# P_06__LPDDR4.net
KiCad netlist of a schematic drawn in Altium Designer
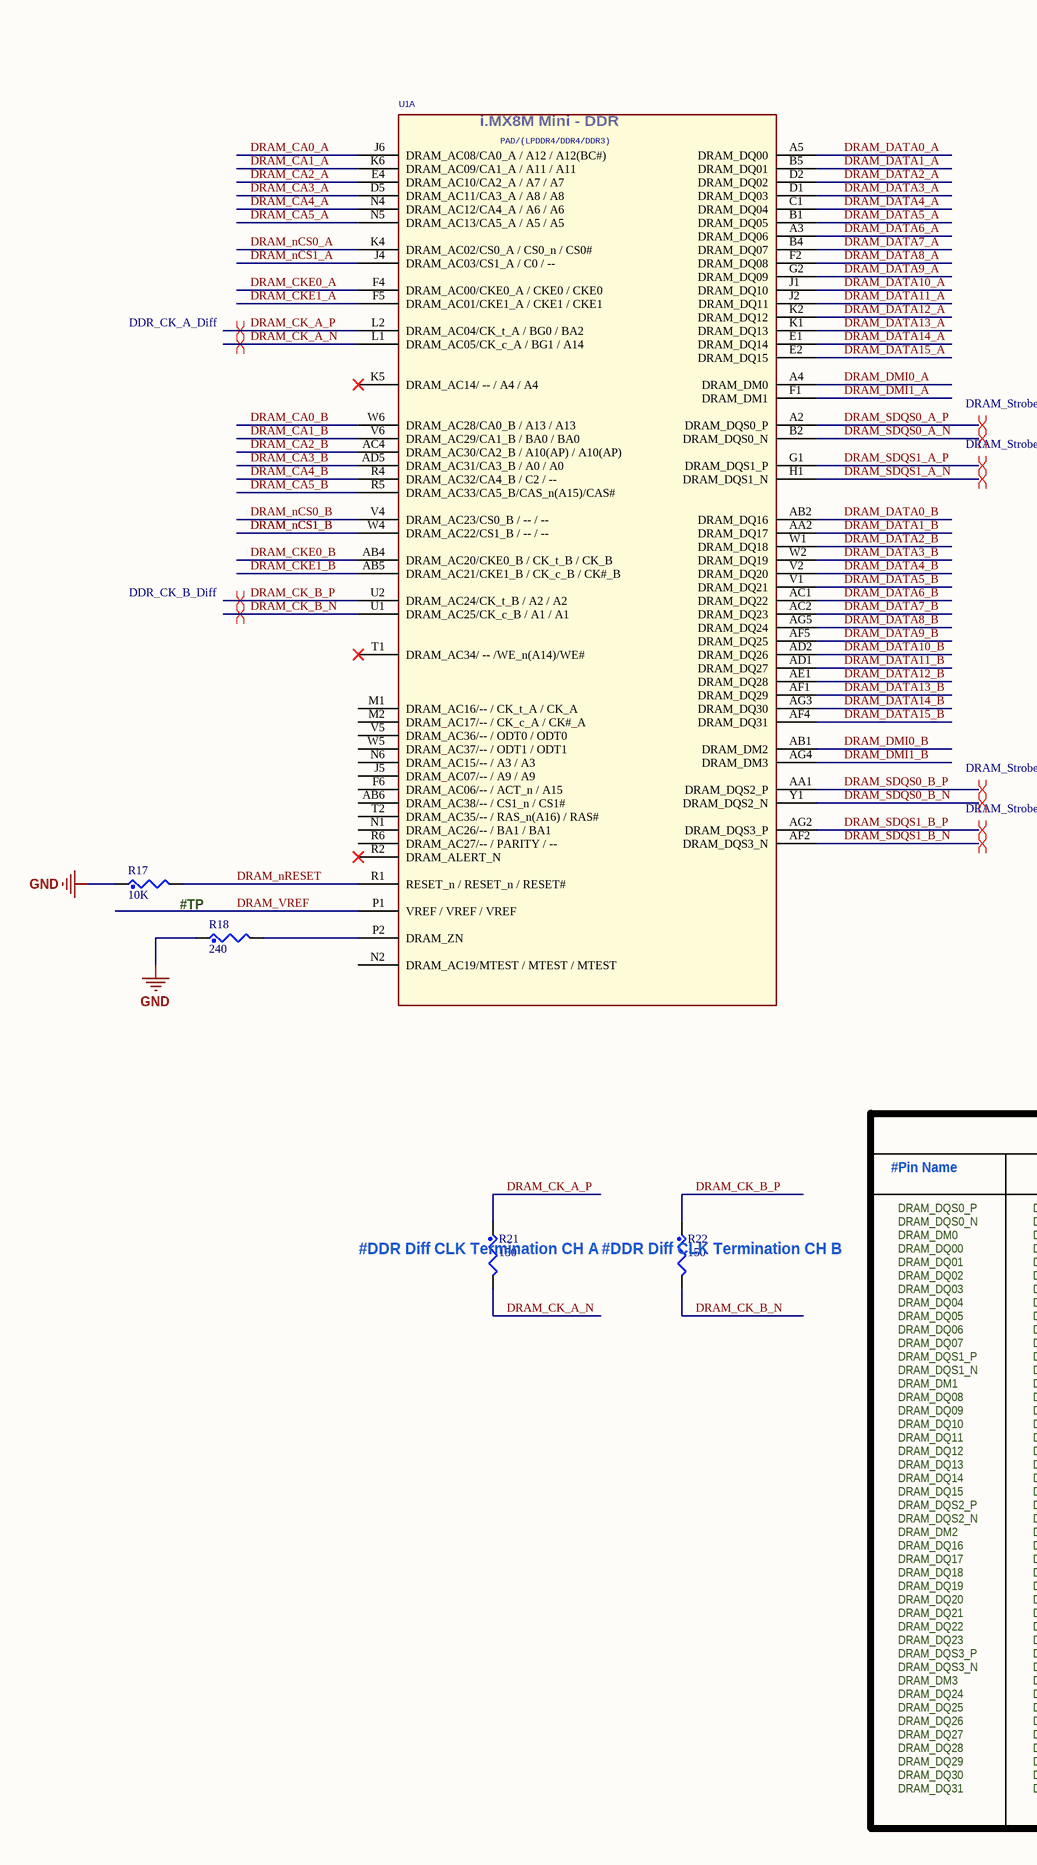
[diagram p0: P[06]_LPDDR4.SchDoc, left]
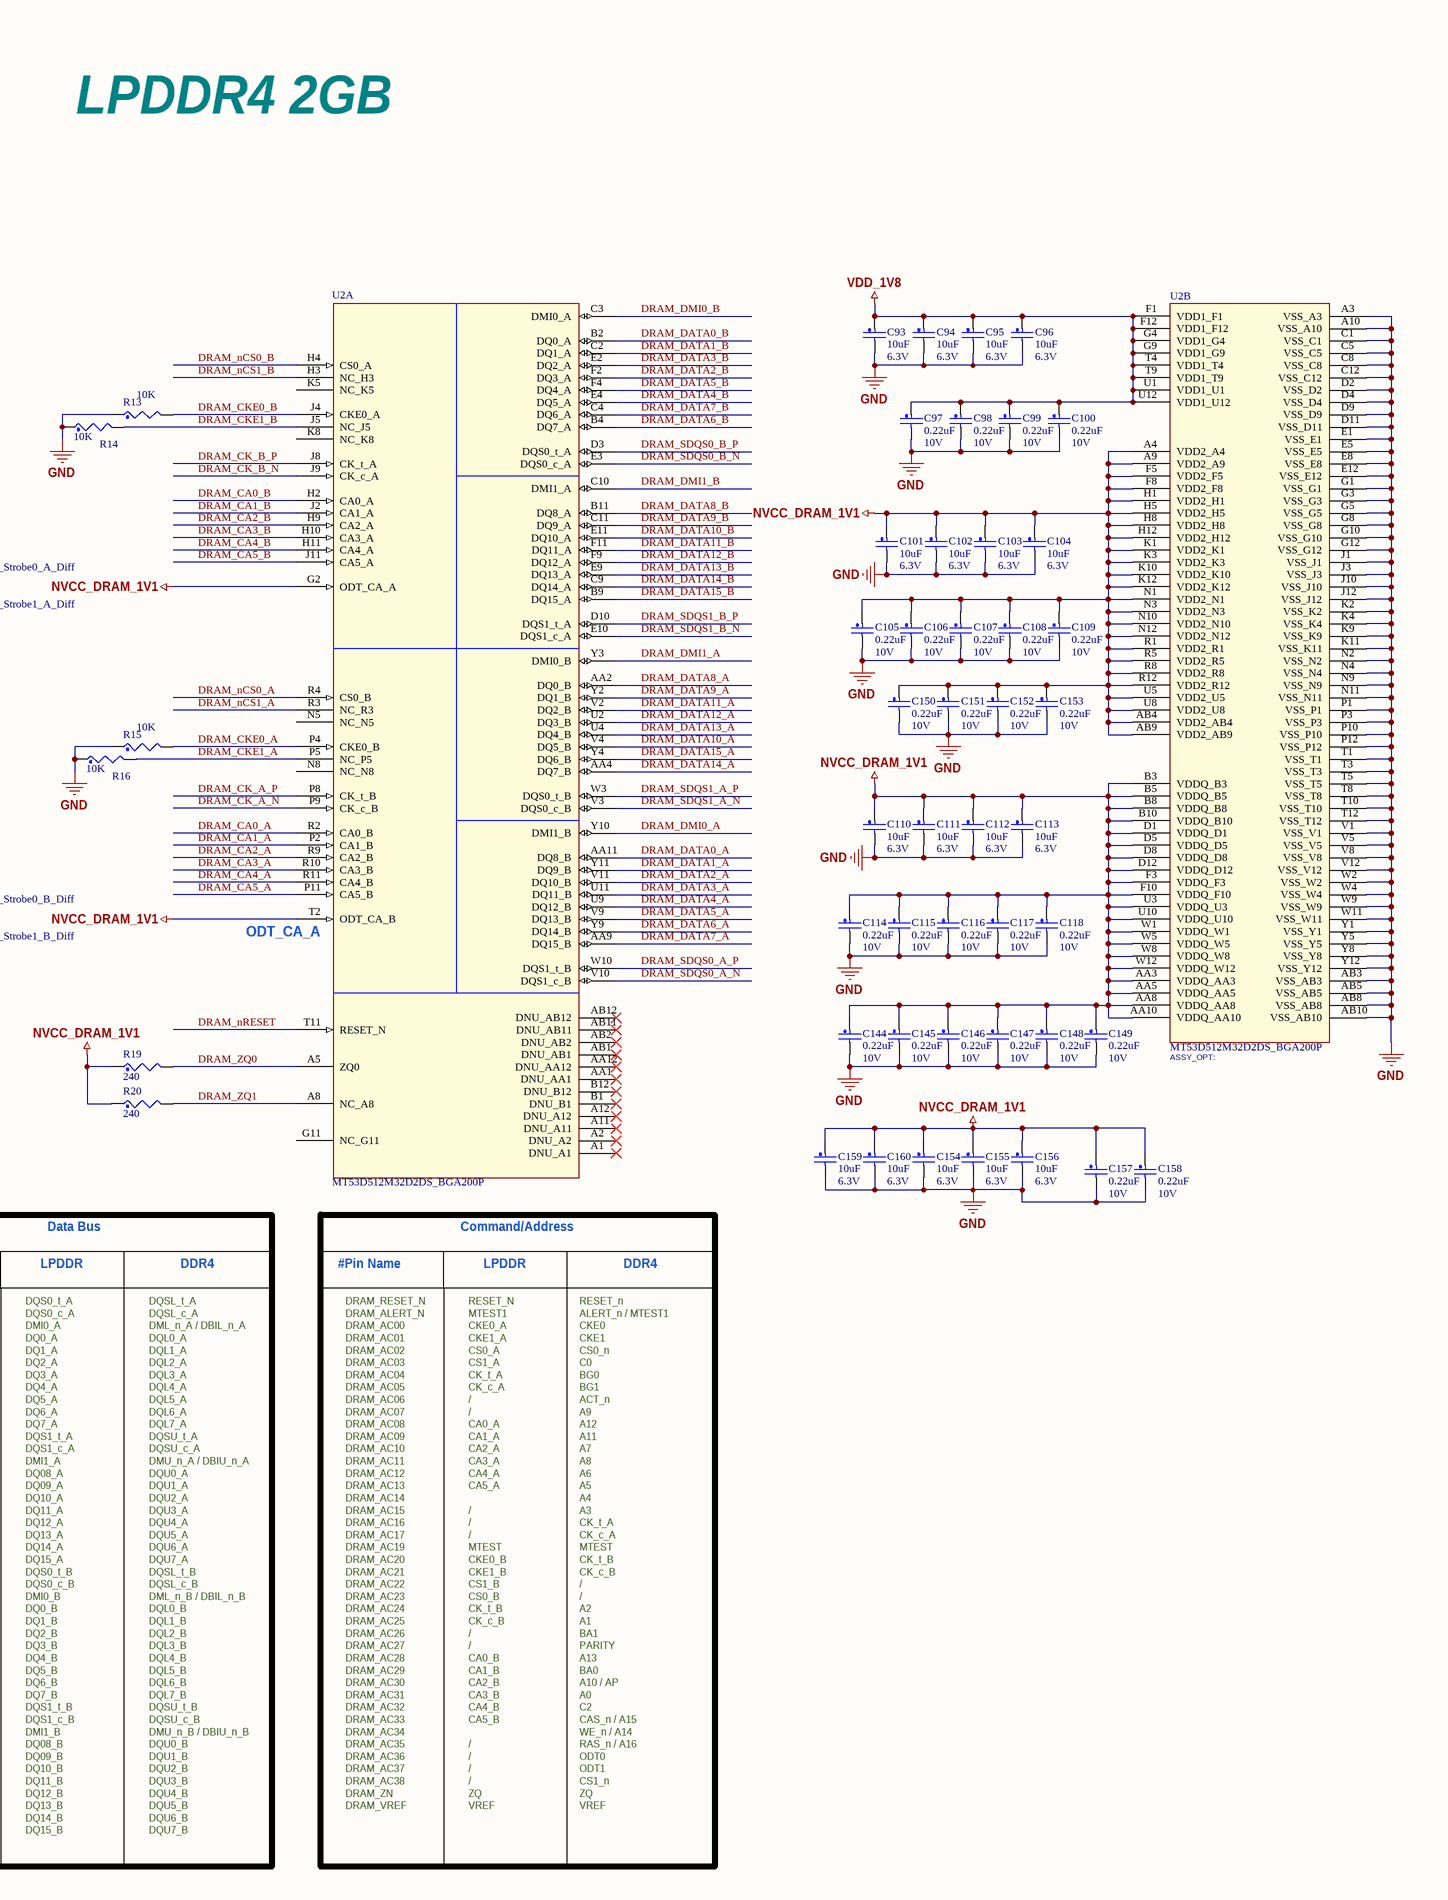
[diagram p1: P[06]_LPDDR4.SchDoc, right]

(export (version "E")
  (design (tool "Eeschema 10.0.6"))
  (components
    (comp (ref "C93")
      (value "10uF")
      (footprint "0402_CC - C")
      (fields (field (name "VOLTAGE") "6.3V"))
      (libsource (lib "AA_iMX8_M_") (part "CAP_NP"))
    )
    (comp (ref "C94")
      (value "10uF")
      (footprint "0402_CC - C")
      (fields (field (name "VOLTAGE") "6.3V"))
      (libsource (lib "AA_iMX8_M_") (part "CAP_NP"))
    )
    (comp (ref "C95")
      (value "10uF")
      (footprint "0402_CC - C")
      (fields (field (name "VOLTAGE") "6.3V"))
      (libsource (lib "AA_iMX8_M_") (part "CAP_NP"))
    )
    (comp (ref "C96")
      (value "10uF")
      (footprint "0402_CC - C")
      (fields (field (name "VOLTAGE") "6.3V"))
      (libsource (lib "AA_iMX8_M_") (part "CAP_NP"))
    )
    (comp (ref "C97")
      (value "0.22uF")
      (footprint "0201_CC - C")
      (fields (field (name "VOLTAGE") "10V"))
      (libsource (lib "AA_iMX8_M_") (part "CAP_NP"))
    )
    (comp (ref "C98")
      (value "0.22uF")
      (footprint "0201_CC - C")
      (fields (field (name "VOLTAGE") "10V"))
      (libsource (lib "AA_iMX8_M_") (part "CAP_NP"))
    )
    (comp (ref "C99")
      (value "0.22uF")
      (footprint "0201_CC - C")
      (fields (field (name "VOLTAGE") "10V"))
      (libsource (lib "AA_iMX8_M_") (part "CAP_NP"))
    )
    (comp (ref "C100")
      (value "0.22uF")
      (footprint "0201_CC - C")
      (fields (field (name "VOLTAGE") "10V"))
      (libsource (lib "AA_iMX8_M_") (part "CAP_NP"))
    )
    (comp (ref "C101")
      (value "10uF")
      (footprint "0402_CC - C")
      (fields (field (name "VOLTAGE") "6.3V"))
      (libsource (lib "AA_iMX8_M_") (part "CAP_NP"))
    )
    (comp (ref "C102")
      (value "10uF")
      (footprint "0402_CC - C")
      (fields (field (name "VOLTAGE") "6.3V"))
      (libsource (lib "AA_iMX8_M_") (part "CAP_NP"))
    )
    (comp (ref "C103")
      (value "10uF")
      (footprint "0402_CC - C")
      (fields (field (name "VOLTAGE") "6.3V"))
      (libsource (lib "AA_iMX8_M_") (part "CAP_NP"))
    )
    (comp (ref "C104")
      (value "10uF")
      (footprint "0402_CC - C")
      (fields (field (name "VOLTAGE") "6.3V"))
      (libsource (lib "AA_iMX8_M_") (part "CAP_NP"))
    )
    (comp (ref "C105")
      (value "0.22uF")
      (footprint "0201_CC - C")
      (fields (field (name "VOLTAGE") "10V"))
      (libsource (lib "AA_iMX8_M_") (part "CAP_NP"))
    )
    (comp (ref "C106")
      (value "0.22uF")
      (footprint "0201_CC - C")
      (fields (field (name "VOLTAGE") "10V"))
      (libsource (lib "AA_iMX8_M_") (part "CAP_NP"))
    )
    (comp (ref "C107")
      (value "0.22uF")
      (footprint "0201_CC - C")
      (fields (field (name "VOLTAGE") "10V"))
      (libsource (lib "AA_iMX8_M_") (part "CAP_NP"))
    )
    (comp (ref "C108")
      (value "0.22uF")
      (footprint "0201_CC - C")
      (fields (field (name "VOLTAGE") "10V"))
      (libsource (lib "AA_iMX8_M_") (part "CAP_NP"))
    )
    (comp (ref "C109")
      (value "0.22uF")
      (footprint "0201_CC - C")
      (fields (field (name "VOLTAGE") "10V"))
      (libsource (lib "AA_iMX8_M_") (part "CAP_NP"))
    )
    (comp (ref "C110")
      (value "10uF")
      (footprint "0402_CC - C")
      (fields (field (name "VOLTAGE") "6.3V"))
      (libsource (lib "AA_iMX8_M_") (part "CAP_NP"))
    )
    (comp (ref "C111")
      (value "10uF")
      (footprint "0402_CC - C")
      (fields (field (name "VOLTAGE") "6.3V"))
      (libsource (lib "AA_iMX8_M_") (part "CAP_NP"))
    )
    (comp (ref "C112")
      (value "10uF")
      (footprint "0402_CC - C")
      (fields (field (name "VOLTAGE") "6.3V"))
      (libsource (lib "AA_iMX8_M_") (part "CAP_NP"))
    )
    (comp (ref "C113")
      (value "10uF")
      (footprint "0402_CC - C")
      (fields (field (name "VOLTAGE") "6.3V"))
      (libsource (lib "AA_iMX8_M_") (part "CAP_NP"))
    )
    (comp (ref "C114")
      (value "0.22uF")
      (footprint "0201_CC - C")
      (fields (field (name "VOLTAGE") "10V"))
      (libsource (lib "AA_iMX8_M_") (part "CAP_NP"))
    )
    (comp (ref "C115")
      (value "0.22uF")
      (footprint "0201_CC - C")
      (fields (field (name "VOLTAGE") "10V"))
      (libsource (lib "AA_iMX8_M_") (part "CAP_NP"))
    )
    (comp (ref "C116")
      (value "0.22uF")
      (footprint "0201_CC - C")
      (fields (field (name "VOLTAGE") "10V"))
      (libsource (lib "AA_iMX8_M_") (part "CAP_NP"))
    )
    (comp (ref "C117")
      (value "0.22uF")
      (footprint "0201_CC - C")
      (fields (field (name "VOLTAGE") "10V"))
      (libsource (lib "AA_iMX8_M_") (part "CAP_NP"))
    )
    (comp (ref "C118")
      (value "0.22uF")
      (footprint "0201_CC - C")
      (fields (field (name "VOLTAGE") "10V"))
      (libsource (lib "AA_iMX8_M_") (part "CAP_NP"))
    )
    (comp (ref "C144")
      (value "0.22uF")
      (footprint "0201_CC - C")
      (fields (field (name "VOLTAGE") "10V"))
      (libsource (lib "AA_iMX8_M_") (part "CAP_NP"))
    )
    (comp (ref "C145")
      (value "0.22uF")
      (footprint "0201_CC - C")
      (fields (field (name "VOLTAGE") "10V"))
      (libsource (lib "AA_iMX8_M_") (part "CAP_NP"))
    )
    (comp (ref "C146")
      (value "0.22uF")
      (footprint "0201_CC - C")
      (fields (field (name "VOLTAGE") "10V"))
      (libsource (lib "AA_iMX8_M_") (part "CAP_NP"))
    )
    (comp (ref "C147")
      (value "0.22uF")
      (footprint "0201_CC - C")
      (fields (field (name "VOLTAGE") "10V"))
      (libsource (lib "AA_iMX8_M_") (part "CAP_NP"))
    )
    (comp (ref "C148")
      (value "0.22uF")
      (footprint "0201_CC - C")
      (fields (field (name "VOLTAGE") "10V"))
      (libsource (lib "AA_iMX8_M_") (part "CAP_NP"))
    )
    (comp (ref "C149")
      (value "0.22uF")
      (footprint "0201_CC - C")
      (fields (field (name "VOLTAGE") "10V"))
      (libsource (lib "AA_iMX8_M_") (part "CAP_NP"))
    )
    (comp (ref "C150")
      (value "0.22uF")
      (footprint "0201_CC - C")
      (fields (field (name "VOLTAGE") "10V"))
      (libsource (lib "AA_iMX8_M_") (part "CAP_NP"))
    )
    (comp (ref "C151")
      (value "0.22uF")
      (footprint "0201_CC - C")
      (fields (field (name "VOLTAGE") "10V"))
      (libsource (lib "AA_iMX8_M_") (part "CAP_NP"))
    )
    (comp (ref "C152")
      (value "0.22uF")
      (footprint "0201_CC - C")
      (fields (field (name "VOLTAGE") "10V"))
      (libsource (lib "AA_iMX8_M_") (part "CAP_NP"))
    )
    (comp (ref "C153")
      (value "0.22uF")
      (footprint "0201_CC - C")
      (fields (field (name "VOLTAGE") "10V"))
      (libsource (lib "AA_iMX8_M_") (part "CAP_NP"))
    )
    (comp (ref "C154")
      (value "10uF")
      (footprint "0402_CC - C")
      (fields (field (name "VOLTAGE") "6.3V"))
      (libsource (lib "AA_iMX8_M_") (part "CAP_NP"))
    )
    (comp (ref "C155")
      (value "10uF")
      (footprint "0402_CC - C")
      (fields (field (name "VOLTAGE") "6.3V"))
      (libsource (lib "AA_iMX8_M_") (part "CAP_NP"))
    )
    (comp (ref "C156")
      (value "10uF")
      (footprint "0402_CC - C")
      (fields (field (name "VOLTAGE") "6.3V"))
      (libsource (lib "AA_iMX8_M_") (part "CAP_NP"))
    )
    (comp (ref "C157")
      (value "0.22uF")
      (footprint "0201_CC - C")
      (fields (field (name "VOLTAGE") "10V"))
      (libsource (lib "AA_iMX8_M_") (part "CAP_NP"))
    )
    (comp (ref "C158")
      (value "0.22uF")
      (footprint "0201_CC - C")
      (fields (field (name "VOLTAGE") "10V"))
      (libsource (lib "AA_iMX8_M_") (part "CAP_NP"))
    )
    (comp (ref "C159")
      (value "10uF")
      (footprint "0402_CC - C")
      (fields (field (name "VOLTAGE") "6.3V"))
      (libsource (lib "AA_iMX8_M_") (part "CAP_NP"))
    )
    (comp (ref "C160")
      (value "10uF")
      (footprint "0402_CC - C")
      (fields (field (name "VOLTAGE") "6.3V"))
      (libsource (lib "AA_iMX8_M_") (part "CAP_NP"))
    )
    (comp (ref "R13") (value "10K") (footprint "0201_CC") (libsource (lib "AA_iMX8_M_") (part "RES")))
    (comp (ref "R14") (value "10K") (footprint "0201_CC") (libsource (lib "AA_iMX8_M_") (part "RES")))
    (comp (ref "R15") (value "10K") (footprint "0201_CC") (libsource (lib "AA_iMX8_M_") (part "RES")))
    (comp (ref "R16") (value "10K") (footprint "0201_CC") (libsource (lib "AA_iMX8_M_") (part "RES")))
    (comp (ref "R17") (value "10K") (footprint "0201_CC") (libsource (lib "AA_iMX8_M_") (part "RES")))
    (comp (ref "R18") (value "240") (footprint "0201_CC") (libsource (lib "AA_iMX8_M_") (part "RES")))
    (comp (ref "R19") (value "240") (footprint "0201_CC") (libsource (lib "AA_iMX8_M_") (part "RES")))
    (comp (ref "R20") (value "240") (footprint "0201_CC") (libsource (lib "AA_iMX8_M_") (part "RES")))
    (comp (ref "R21") (value "150") (footprint "0402_CC") (libsource (lib "AA_iMX8_M_") (part "RES")))
    (comp (ref "R22") (value "150") (footprint "0402_CC") (libsource (lib "AA_iMX8_M_") (part "RES")))
    (comp (ref "U1")
      (value "~")
      (footprint "BGA486_0P5_14X14")
      (description "IC CPU QUAD CORTEX A53+M4 1.8GHZ BGA486 / By Arman Arvand")
      (libsource (lib "AA_iMX8_M_") (part "MIMX8MM_BGA486P"))
    )
    (comp (ref "U2")
      (value "MT53D512M32D2DS_BGA200P")
      (footprint "BGA200_0P65X0P8_10P1X14P6")
      (description "MT53D512M32D2DS_BGA200P\\By AAR")
      (libsource (lib "AA_iMX8_M_") (part "MT53D512M32D2DS_BGA200P"))
    )
  )
  (nets
    (net (code "1") (name "/DRAM_CA0_A") (class "Default")
      (node (ref "U1") (pin "J6") (pinfunction "DRAM_AC08/CA0_A_/_A12_/_A12(BC#)_J6") (pintype "passive"))
      (node (ref "U2") (pin "R2") (pinfunction "CA0_B_R2") (pintype "input"))
    )
    (net (code "2") (name "/DRAM_CA0_B") (class "Default")
      (node (ref "U1") (pin "W6") (pinfunction "DRAM_AC28/CA0_B_/_A13_/_A13_W6") (pintype "passive"))
      (node (ref "U2") (pin "H2") (pinfunction "CA0_A_H2") (pintype "input"))
    )
    (net (code "3") (name "/DRAM_CA1_A") (class "Default")
      (node (ref "U1") (pin "K6") (pinfunction "DRAM_AC09/CA1_A_/_A11_/_A11_K6") (pintype "passive"))
      (node (ref "U2") (pin "P2") (pinfunction "CA1_B_P2") (pintype "input"))
    )
    (net (code "4") (name "/DRAM_CA1_B") (class "Default")
      (node (ref "U1") (pin "V6") (pinfunction "DRAM_AC29/CA1_B_/_BA0_/_BA0_V6") (pintype "passive"))
      (node (ref "U2") (pin "J2") (pinfunction "CA1_A_J2") (pintype "input"))
    )
    (net (code "5") (name "/DRAM_CA2_A") (class "Default")
      (node (ref "U1") (pin "E4") (pinfunction "DRAM_AC10/CA2_A_/_A7_/_A7_E4") (pintype "passive"))
      (node (ref "U2") (pin "R9") (pinfunction "CA2_B_R9") (pintype "input"))
    )
    (net (code "6") (name "/DRAM_CA2_B") (class "Default")
      (node (ref "U1") (pin "AC4") (pinfunction "DRAM_AC30/CA2_B_/_A10(AP)_/_A10(AP)_AC4") (pintype "passive"))
      (node (ref "U2") (pin "H9") (pinfunction "CA2_A_H9") (pintype "input"))
    )
    (net (code "7") (name "/DRAM_CA3_A") (class "Default")
      (node (ref "U1") (pin "D5") (pinfunction "DRAM_AC11/CA3_A_/_A8_/_A8_D5") (pintype "passive"))
      (node (ref "U2") (pin "R10") (pinfunction "CA3_B_R10") (pintype "input"))
    )
    (net (code "8") (name "/DRAM_CA3_B") (class "Default")
      (node (ref "U1") (pin "AD5") (pinfunction "DRAM_AC31/CA3_B_/_A0_/_A0_AD5") (pintype "passive"))
      (node (ref "U2") (pin "H10") (pinfunction "CA3_A_H10") (pintype "input"))
    )
    (net (code "9") (name "/DRAM_CA4_A") (class "Default")
      (node (ref "U1") (pin "N4") (pinfunction "DRAM_AC12/CA4_A_/_A6_/_A6_N4") (pintype "passive"))
      (node (ref "U2") (pin "R11") (pinfunction "CA4_B_R11") (pintype "input"))
    )
    (net (code "10") (name "/DRAM_CA4_B") (class "Default")
      (node (ref "U1") (pin "R4") (pinfunction "DRAM_AC32/CA4_B_/_C2_/_--_R4") (pintype "passive"))
      (node (ref "U2") (pin "H11") (pinfunction "CA4_A_H11") (pintype "input"))
    )
    (net (code "11") (name "/DRAM_CA5_A") (class "Default")
      (node (ref "U1") (pin "N5") (pinfunction "DRAM_AC13/CA5_A_/_A5_/_A5_N5") (pintype "passive"))
      (node (ref "U2") (pin "P11") (pinfunction "CA5_B_P11") (pintype "input"))
    )
    (net (code "12") (name "/DRAM_CA5_B") (class "Default")
      (node (ref "U1") (pin "R5") (pinfunction "DRAM_AC33/CA5_B/CAS_n(A15)/CAS#_R5") (pintype "passive"))
      (node (ref "U2") (pin "J11") (pinfunction "CA5_A_J11") (pintype "input"))
    )
    (net (code "13") (name "/DRAM_CKE0_A") (class "Default")
      (node (ref "R15") (pin "2") (pinfunction "2_2") (pintype "passive"))
      (node (ref "U1") (pin "F4") (pinfunction "DRAM_AC00/CKE0_A_/_CKE0_/_CKE0_F4") (pintype "passive"))
      (node (ref "U2") (pin "P4") (pinfunction "CKE0_B_P4") (pintype "input"))
    )
    (net (code "14") (name "/DRAM_CKE0_B") (class "Default")
      (node (ref "R13") (pin "2") (pinfunction "2_2") (pintype "passive"))
      (node (ref "U1") (pin "AB4") (pinfunction "DRAM_AC20/CKE0_B_/_CK_t_B_/_CK_B_AB4") (pintype "passive"))
      (node (ref "U2") (pin "J4") (pinfunction "CKE0_A_J4") (pintype "input"))
    )
    (net (code "15") (name "/DRAM_CKE1_A") (class "Default")
      (node (ref "R16") (pin "2") (pinfunction "2_2") (pintype "passive"))
      (node (ref "U1") (pin "F5") (pinfunction "DRAM_AC01/CKE1_A_/_CKE1_/_CKE1_F5") (pintype "passive"))
      (node (ref "U2") (pin "P5") (pinfunction "NC_P5_P5") (pintype "passive"))
    )
    (net (code "16") (name "/DRAM_CKE1_B") (class "Default")
      (node (ref "R14") (pin "2") (pinfunction "2_2") (pintype "passive"))
      (node (ref "U1") (pin "AB5") (pinfunction "DRAM_AC21/CKE1_B_/_CK_c_B_/_CK#_B_AB5") (pintype "passive"))
      (node (ref "U2") (pin "J5") (pinfunction "NC_J5_J5") (pintype "passive"))
    )
    (net (code "17") (name "/DRAM_CK_A_N") (class "Default")
      (node (ref "R21") (pin "2") (pinfunction "2_2") (pintype "passive"))
      (node (ref "U1") (pin "L1") (pinfunction "DRAM_AC05/CK_c_A_/_BG1_/_A14_L1") (pintype "passive"))
      (node (ref "U2") (pin "P9") (pinfunction "CK_c_B_P9") (pintype "input"))
    )
    (net (code "18") (name "/DRAM_CK_A_P") (class "Default")
      (node (ref "R21") (pin "1") (pinfunction "1_1") (pintype "passive"))
      (node (ref "U1") (pin "L2") (pinfunction "DRAM_AC04/CK_t_A_/_BG0_/_BA2_L2") (pintype "passive"))
      (node (ref "U2") (pin "P8") (pinfunction "CK_t_B_P8") (pintype "input"))
    )
    (net (code "19") (name "/DRAM_CK_B_N") (class "Default")
      (node (ref "R22") (pin "2") (pinfunction "2_2") (pintype "passive"))
      (node (ref "U1") (pin "U1") (pinfunction "DRAM_AC25/CK_c_B_/_A1_/_A1_U1") (pintype "passive"))
      (node (ref "U2") (pin "J9") (pinfunction "CK_c_A_J9") (pintype "input"))
    )
    (net (code "20") (name "/DRAM_CK_B_P") (class "Default")
      (node (ref "R22") (pin "1") (pinfunction "1_1") (pintype "passive"))
      (node (ref "U1") (pin "U2") (pinfunction "DRAM_AC24/CK_t_B_/_A2_/_A2_U2") (pintype "passive"))
      (node (ref "U2") (pin "J8") (pinfunction "CK_t_A_J8") (pintype "input"))
    )
    (net (code "21") (name "/DRAM_DATA0_A") (class "Default")
      (node (ref "U1") (pin "A5") (pinfunction "DRAM_DQ00_A5") (pintype "passive"))
      (node (ref "U2") (pin "AA11") (pinfunction "DQ8_B_AA11") (pintype "bidirectional"))
    )
    (net (code "22") (name "/DRAM_DATA0_B") (class "Default")
      (node (ref "U1") (pin "AB2") (pinfunction "DRAM_DQ16_AB2") (pintype "passive"))
      (node (ref "U2") (pin "B2") (pinfunction "DQ0_A_B2") (pintype "bidirectional"))
    )
    (net (code "23") (name "/DRAM_DATA1_A") (class "Default")
      (node (ref "U1") (pin "B5") (pinfunction "DRAM_DQ01_B5") (pintype "passive"))
      (node (ref "U2") (pin "Y11") (pinfunction "DQ9_B_Y11") (pintype "bidirectional"))
    )
    (net (code "24") (name "/DRAM_DATA1_B") (class "Default")
      (node (ref "U1") (pin "AA2") (pinfunction "DRAM_DQ17_AA2") (pintype "passive"))
      (node (ref "U2") (pin "C2") (pinfunction "DQ1_A_C2") (pintype "bidirectional"))
    )
    (net (code "25") (name "/DRAM_DATA2_A") (class "Default")
      (node (ref "U1") (pin "D2") (pinfunction "DRAM_DQ02_D2") (pintype "passive"))
      (node (ref "U2") (pin "V11") (pinfunction "DQ10_B_V11") (pintype "bidirectional"))
    )
    (net (code "26") (name "/DRAM_DATA2_B") (class "Default")
      (node (ref "U1") (pin "W1") (pinfunction "DRAM_DQ18_W1") (pintype "passive"))
      (node (ref "U2") (pin "F2") (pinfunction "DQ3_A_F2") (pintype "bidirectional"))
    )
    (net (code "27") (name "/DRAM_DATA3_A") (class "Default")
      (node (ref "U1") (pin "D1") (pinfunction "DRAM_DQ03_D1") (pintype "passive"))
      (node (ref "U2") (pin "U11") (pinfunction "DQ11_B_U11") (pintype "bidirectional"))
    )
    (net (code "28") (name "/DRAM_DATA3_B") (class "Default")
      (node (ref "U1") (pin "W2") (pinfunction "DRAM_DQ19_W2") (pintype "passive"))
      (node (ref "U2") (pin "E2") (pinfunction "DQ2_A_E2") (pintype "bidirectional"))
    )
    (net (code "29") (name "/DRAM_DATA4_A") (class "Default")
      (node (ref "U1") (pin "C1") (pinfunction "DRAM_DQ04_C1") (pintype "passive"))
      (node (ref "U2") (pin "U9") (pinfunction "DQ12_B_U9") (pintype "bidirectional"))
    )
    (net (code "30") (name "/DRAM_DATA4_B") (class "Default")
      (node (ref "U1") (pin "V2") (pinfunction "DRAM_DQ20_V2") (pintype "passive"))
      (node (ref "U2") (pin "E4") (pinfunction "DQ5_A_E4") (pintype "bidirectional"))
    )
    (net (code "31") (name "/DRAM_DATA5_A") (class "Default")
      (node (ref "U1") (pin "B1") (pinfunction "DRAM_DQ05_B1") (pintype "passive"))
      (node (ref "U2") (pin "V9") (pinfunction "DQ13_B_V9") (pintype "bidirectional"))
    )
    (net (code "32") (name "/DRAM_DATA5_B") (class "Default")
      (node (ref "U1") (pin "V1") (pinfunction "DRAM_DQ21_V1") (pintype "passive"))
      (node (ref "U2") (pin "F4") (pinfunction "DQ4_A_F4") (pintype "bidirectional"))
    )
    (net (code "33") (name "/DRAM_DATA6_A") (class "Default")
      (node (ref "U1") (pin "A3") (pinfunction "DRAM_DQ06_A3") (pintype "passive"))
      (node (ref "U2") (pin "Y9") (pinfunction "DQ14_B_Y9") (pintype "bidirectional"))
    )
    (net (code "34") (name "/DRAM_DATA6_B") (class "Default")
      (node (ref "U1") (pin "AC1") (pinfunction "DRAM_DQ22_AC1") (pintype "passive"))
      (node (ref "U2") (pin "B4") (pinfunction "DQ7_A_B4") (pintype "bidirectional"))
    )
    (net (code "35") (name "/DRAM_DATA7_A") (class "Default")
      (node (ref "U1") (pin "B4") (pinfunction "DRAM_DQ07_B4") (pintype "passive"))
      (node (ref "U2") (pin "AA9") (pinfunction "DQ15_B_AA9") (pintype "bidirectional"))
    )
    (net (code "36") (name "/DRAM_DATA7_B") (class "Default")
      (node (ref "U1") (pin "AC2") (pinfunction "DRAM_DQ23_AC2") (pintype "passive"))
      (node (ref "U2") (pin "C4") (pinfunction "DQ6_A_C4") (pintype "bidirectional"))
    )
    (net (code "37") (name "/DRAM_DATA8_A") (class "Default")
      (node (ref "U1") (pin "F2") (pinfunction "DRAM_DQ08_F2") (pintype "passive"))
      (node (ref "U2") (pin "AA2") (pinfunction "DQ0_B_AA2") (pintype "bidirectional"))
    )
    (net (code "38") (name "/DRAM_DATA8_B") (class "Default")
      (node (ref "U1") (pin "AG5") (pinfunction "DRAM_DQ24_AG5") (pintype "passive"))
      (node (ref "U2") (pin "B11") (pinfunction "DQ8_A_B11") (pintype "bidirectional"))
    )
    (net (code "39") (name "/DRAM_DATA9_A") (class "Default")
      (node (ref "U1") (pin "G2") (pinfunction "DRAM_DQ09_G2") (pintype "passive"))
      (node (ref "U2") (pin "Y2") (pinfunction "DQ1_B_Y2") (pintype "bidirectional"))
    )
    (net (code "40") (name "/DRAM_DATA9_B") (class "Default")
      (node (ref "U1") (pin "AF5") (pinfunction "DRAM_DQ25_AF5") (pintype "passive"))
      (node (ref "U2") (pin "C11") (pinfunction "DQ9_A_C11") (pintype "bidirectional"))
    )
    (net (code "41") (name "/DRAM_DATA10_A") (class "Default")
      (node (ref "U1") (pin "J1") (pinfunction "DRAM_DQ10_J1") (pintype "passive"))
      (node (ref "U2") (pin "V4") (pinfunction "DQ5_B_V4") (pintype "bidirectional"))
    )
    (net (code "42") (name "/DRAM_DATA10_B") (class "Default")
      (node (ref "U1") (pin "AD2") (pinfunction "DRAM_DQ26_AD2") (pintype "passive"))
      (node (ref "U2") (pin "E11") (pinfunction "DQ10_A_E11") (pintype "bidirectional"))
    )
    (net (code "43") (name "/DRAM_DATA11_A") (class "Default")
      (node (ref "U1") (pin "J2") (pinfunction "DRAM_DQ11_J2") (pintype "passive"))
      (node (ref "U2") (pin "V2") (pinfunction "DQ2_B_V2") (pintype "bidirectional"))
    )
    (net (code "44") (name "/DRAM_DATA11_B") (class "Default")
      (node (ref "U1") (pin "AD1") (pinfunction "DRAM_DQ27_AD1") (pintype "passive"))
      (node (ref "U2") (pin "F11") (pinfunction "DQ11_A_F11") (pintype "bidirectional"))
    )
    (net (code "45") (name "/DRAM_DATA12_A") (class "Default")
      (node (ref "U1") (pin "K2") (pinfunction "DRAM_DQ12_K2") (pintype "passive"))
      (node (ref "U2") (pin "U2") (pinfunction "DQ3_B_U2") (pintype "bidirectional"))
    )
    (net (code "46") (name "/DRAM_DATA12_B") (class "Default")
      (node (ref "U1") (pin "AE1") (pinfunction "DRAM_DQ28_AE1") (pintype "passive"))
      (node (ref "U2") (pin "F9") (pinfunction "DQ12_A_F9") (pintype "bidirectional"))
    )
    (net (code "47") (name "/DRAM_DATA13_A") (class "Default")
      (node (ref "U1") (pin "K1") (pinfunction "DRAM_DQ13_K1") (pintype "passive"))
      (node (ref "U2") (pin "U4") (pinfunction "DQ4_B_U4") (pintype "bidirectional"))
    )
    (net (code "48") (name "/DRAM_DATA13_B") (class "Default")
      (node (ref "U1") (pin "AF1") (pinfunction "DRAM_DQ29_AF1") (pintype "passive"))
      (node (ref "U2") (pin "E9") (pinfunction "DQ13_A_E9") (pintype "bidirectional"))
    )
    (net (code "49") (name "/DRAM_DATA14_A") (class "Default")
      (node (ref "U1") (pin "E1") (pinfunction "DRAM_DQ14_E1") (pintype "passive"))
      (node (ref "U2") (pin "AA4") (pinfunction "DQ7_B_AA4") (pintype "bidirectional"))
    )
    (net (code "50") (name "/DRAM_DATA14_B") (class "Default")
      (node (ref "U1") (pin "AG3") (pinfunction "DRAM_DQ30_AG3") (pintype "passive"))
      (node (ref "U2") (pin "C9") (pinfunction "DQ14_A_C9") (pintype "bidirectional"))
    )
    (net (code "51") (name "/DRAM_DATA15_A") (class "Default")
      (node (ref "U1") (pin "E2") (pinfunction "DRAM_DQ15_E2") (pintype "passive"))
      (node (ref "U2") (pin "Y4") (pinfunction "DQ6_B_Y4") (pintype "bidirectional"))
    )
    (net (code "52") (name "/DRAM_DATA15_B") (class "Default")
      (node (ref "U1") (pin "AF4") (pinfunction "DRAM_DQ31_AF4") (pintype "passive"))
      (node (ref "U2") (pin "B9") (pinfunction "DQ15_A_B9") (pintype "bidirectional"))
    )
    (net (code "53") (name "/DRAM_DMI0_A") (class "Default")
      (node (ref "U1") (pin "A4") (pinfunction "DRAM_DM0_A4") (pintype "passive"))
      (node (ref "U2") (pin "Y10") (pinfunction "DMI1_B_Y10") (pintype "bidirectional"))
    )
    (net (code "54") (name "/DRAM_DMI0_B") (class "Default")
      (node (ref "U1") (pin "AB1") (pinfunction "DRAM_DM2_AB1") (pintype "passive"))
      (node (ref "U2") (pin "C3") (pinfunction "DMI0_A_C3") (pintype "bidirectional"))
    )
    (net (code "55") (name "/DRAM_DMI1_A") (class "Default")
      (node (ref "U1") (pin "F1") (pinfunction "DRAM_DM1_F1") (pintype "passive"))
      (node (ref "U2") (pin "Y3") (pinfunction "DMI0_B_Y3") (pintype "bidirectional"))
    )
    (net (code "56") (name "/DRAM_DMI1_B") (class "Default")
      (node (ref "U1") (pin "AG4") (pinfunction "DRAM_DM3_AG4") (pintype "passive"))
      (node (ref "U2") (pin "C10") (pinfunction "DMI1_A_C10") (pintype "bidirectional"))
    )
    (net (code "57") (name "/DRAM_SDQS0_A_N") (class "Default")
      (node (ref "U1") (pin "B2") (pinfunction "DRAM_DQS0_N_B2") (pintype "passive"))
      (node (ref "U2") (pin "V10") (pinfunction "DQS1_c_B_V10") (pintype "bidirectional"))
    )
    (net (code "58") (name "/DRAM_SDQS0_A_P") (class "Default")
      (node (ref "U1") (pin "A2") (pinfunction "DRAM_DQS0_P_A2") (pintype "passive"))
      (node (ref "U2") (pin "W10") (pinfunction "DQS1_t_B_W10") (pintype "bidirectional"))
    )
    (net (code "59") (name "/DRAM_SDQS0_B_N") (class "Default")
      (node (ref "U1") (pin "Y1") (pinfunction "DRAM_DQS2_N_Y1") (pintype "passive"))
      (node (ref "U2") (pin "E3") (pinfunction "DQS0_c_A_E3") (pintype "bidirectional"))
    )
    (net (code "60") (name "/DRAM_SDQS0_B_P") (class "Default")
      (node (ref "U1") (pin "AA1") (pinfunction "DRAM_DQS2_P_AA1") (pintype "passive"))
      (node (ref "U2") (pin "D3") (pinfunction "DQS0_t_A_D3") (pintype "bidirectional"))
    )
    (net (code "61") (name "/DRAM_SDQS1_A_N") (class "Default")
      (node (ref "U1") (pin "H1") (pinfunction "DRAM_DQS1_N_H1") (pintype "passive"))
      (node (ref "U2") (pin "V3") (pinfunction "DQS0_c_B_V3") (pintype "bidirectional"))
    )
    (net (code "62") (name "/DRAM_SDQS1_A_P") (class "Default")
      (node (ref "U1") (pin "G1") (pinfunction "DRAM_DQS1_P_G1") (pintype "passive"))
      (node (ref "U2") (pin "W3") (pinfunction "DQS0_t_B_W3") (pintype "bidirectional"))
    )
    (net (code "63") (name "/DRAM_SDQS1_B_N") (class "Default")
      (node (ref "U1") (pin "AF2") (pinfunction "DRAM_DQS3_N_AF2") (pintype "passive"))
      (node (ref "U2") (pin "E10") (pinfunction "DQS1_c_A_E10") (pintype "bidirectional"))
    )
    (net (code "64") (name "/DRAM_SDQS1_B_P") (class "Default")
      (node (ref "U1") (pin "AG2") (pinfunction "DRAM_DQS3_P_AG2") (pintype "passive"))
      (node (ref "U2") (pin "D10") (pinfunction "DQS1_t_A_D10") (pintype "bidirectional"))
    )
    (net (code "65") (name "/DRAM_VREF") (class "Default")
      (node (ref "U1") (pin "P1") (pinfunction "VREF_/_VREF_/_VREF_P1") (pintype "passive"))
    )
    (net (code "66") (name "/DRAM_ZQ0") (class "Default")
      (node (ref "R19") (pin "2") (pinfunction "2_2") (pintype "passive"))
      (node (ref "U2") (pin "A5") (pinfunction "ZQ0_A5") (pintype "passive"))
    )
    (net (code "67") (name "/DRAM_ZQ1") (class "Default")
      (node (ref "R20") (pin "2") (pinfunction "2_2") (pintype "passive"))
      (node (ref "U2") (pin "A8") (pinfunction "NC_A8_A8") (pintype "passive"))
    )
    (net (code "68") (name "/DRAM_nCS0_A") (class "Default")
      (node (ref "U1") (pin "K4") (pinfunction "DRAM_AC02/CS0_A_/_CS0_n_/_CS0#_K4") (pintype "passive"))
      (node (ref "U2") (pin "R4") (pinfunction "CS0_B_R4") (pintype "input"))
    )
    (net (code "69") (name "/DRAM_nCS0_B") (class "Default")
      (node (ref "U1") (pin "V4") (pinfunction "DRAM_AC23/CS0_B_/_--_/_--_V4") (pintype "passive"))
      (node (ref "U2") (pin "H4") (pinfunction "CS0_A_H4") (pintype "input"))
    )
    (net (code "70") (name "/DRAM_nCS1_A") (class "Default")
      (node (ref "U1") (pin "J4") (pinfunction "DRAM_AC03/CS1_A_/_C0_/_--_J4") (pintype "passive"))
      (node (ref "U2") (pin "R3") (pinfunction "NC_R3_R3") (pintype "passive"))
    )
    (net (code "71") (name "/DRAM_nCS1_B") (class "Default")
      (node (ref "U1") (pin "W4") (pinfunction "DRAM_AC22/CS1_B_/_--_/_--_W4") (pintype "passive"))
      (node (ref "U2") (pin "H3") (pinfunction "NC_H3_H3") (pintype "passive"))
    )
    (net (code "72") (name "/DRAM_nRESET") (class "Default")
      (node (ref "R17") (pin "2") (pinfunction "2_2") (pintype "passive"))
      (node (ref "U1") (pin "R1") (pinfunction "RESET_n_/_RESET_n_/_RESET#_R1") (pintype "passive"))
      (node (ref "U2") (pin "T11") (pinfunction "RESET_N_T11") (pintype "input"))
    )
    (net (code "73") (name "GND") (class "Default")
      (node (ref "C100") (pin "2") (pinfunction "2_2") (pintype "passive"))
      (node (ref "C101") (pin "2") (pinfunction "2_2") (pintype "passive"))
      (node (ref "C102") (pin "2") (pinfunction "2_2") (pintype "passive"))
      (node (ref "C103") (pin "2") (pinfunction "2_2") (pintype "passive"))
      (node (ref "C104") (pin "2") (pinfunction "2_2") (pintype "passive"))
      (node (ref "C105") (pin "2") (pinfunction "2_2") (pintype "passive"))
      (node (ref "C106") (pin "2") (pinfunction "2_2") (pintype "passive"))
      (node (ref "C107") (pin "2") (pinfunction "2_2") (pintype "passive"))
      (node (ref "C108") (pin "2") (pinfunction "2_2") (pintype "passive"))
      (node (ref "C109") (pin "2") (pinfunction "2_2") (pintype "passive"))
      (node (ref "C110") (pin "2") (pinfunction "2_2") (pintype "passive"))
      (node (ref "C111") (pin "2") (pinfunction "2_2") (pintype "passive"))
      (node (ref "C112") (pin "2") (pinfunction "2_2") (pintype "passive"))
      (node (ref "C113") (pin "2") (pinfunction "2_2") (pintype "passive"))
      (node (ref "C114") (pin "2") (pinfunction "2_2") (pintype "passive"))
      (node (ref "C115") (pin "2") (pinfunction "2_2") (pintype "passive"))
      (node (ref "C116") (pin "2") (pinfunction "2_2") (pintype "passive"))
      (node (ref "C117") (pin "2") (pinfunction "2_2") (pintype "passive"))
      (node (ref "C118") (pin "2") (pinfunction "2_2") (pintype "passive"))
      (node (ref "C144") (pin "2") (pinfunction "2_2") (pintype "passive"))
      (node (ref "C145") (pin "2") (pinfunction "2_2") (pintype "passive"))
      (node (ref "C146") (pin "2") (pinfunction "2_2") (pintype "passive"))
      (node (ref "C147") (pin "2") (pinfunction "2_2") (pintype "passive"))
      (node (ref "C148") (pin "2") (pinfunction "2_2") (pintype "passive"))
      (node (ref "C149") (pin "2") (pinfunction "2_2") (pintype "passive"))
      (node (ref "C150") (pin "2") (pinfunction "2_2") (pintype "passive"))
      (node (ref "C151") (pin "2") (pinfunction "2_2") (pintype "passive"))
      (node (ref "C152") (pin "2") (pinfunction "2_2") (pintype "passive"))
      (node (ref "C153") (pin "2") (pinfunction "2_2") (pintype "passive"))
      (node (ref "C154") (pin "2") (pinfunction "2_2") (pintype "passive"))
      (node (ref "C155") (pin "2") (pinfunction "2_2") (pintype "passive"))
      (node (ref "C156") (pin "2") (pinfunction "2_2") (pintype "passive"))
      (node (ref "C157") (pin "2") (pinfunction "2_2") (pintype "passive"))
      (node (ref "C158") (pin "2") (pinfunction "2_2") (pintype "passive"))
      (node (ref "C159") (pin "2") (pinfunction "2_2") (pintype "passive"))
      (node (ref "C160") (pin "2") (pinfunction "2_2") (pintype "passive"))
      (node (ref "C93") (pin "2") (pinfunction "2_2") (pintype "passive"))
      (node (ref "C94") (pin "2") (pinfunction "2_2") (pintype "passive"))
      (node (ref "C95") (pin "2") (pinfunction "2_2") (pintype "passive"))
      (node (ref "C96") (pin "2") (pinfunction "2_2") (pintype "passive"))
      (node (ref "C97") (pin "2") (pinfunction "2_2") (pintype "passive"))
      (node (ref "C98") (pin "2") (pinfunction "2_2") (pintype "passive"))
      (node (ref "C99") (pin "2") (pinfunction "2_2") (pintype "passive"))
      (node (ref "R13") (pin "1") (pinfunction "1_1") (pintype "passive"))
      (node (ref "R14") (pin "1") (pinfunction "1_1") (pintype "passive"))
      (node (ref "R15") (pin "1") (pinfunction "1_1") (pintype "passive"))
      (node (ref "R16") (pin "1") (pinfunction "1_1") (pintype "passive"))
      (node (ref "R17") (pin "1") (pinfunction "1_1") (pintype "passive"))
      (node (ref "R18") (pin "1") (pinfunction "1_1") (pintype "passive"))
      (node (ref "U2") (pin "A10") (pinfunction "VSS_A10_A10") (pintype "power_in"))
      (node (ref "U2") (pin "A3") (pinfunction "VSS_A3_A3") (pintype "power_in"))
      (node (ref "U2") (pin "AB10") (pinfunction "VSS_AB10_AB10") (pintype "power_in"))
      (node (ref "U2") (pin "AB3") (pinfunction "VSS_AB3_AB3") (pintype "power_in"))
      (node (ref "U2") (pin "AB5") (pinfunction "VSS_AB5_AB5") (pintype "power_in"))
      (node (ref "U2") (pin "AB8") (pinfunction "VSS_AB8_AB8") (pintype "power_in"))
      (node (ref "U2") (pin "C1") (pinfunction "VSS_C1_C1") (pintype "power_in"))
      (node (ref "U2") (pin "C12") (pinfunction "VSS_C12_C12") (pintype "power_in"))
      (node (ref "U2") (pin "C5") (pinfunction "VSS_C5_C5") (pintype "power_in"))
      (node (ref "U2") (pin "C8") (pinfunction "VSS_C8_C8") (pintype "power_in"))
      (node (ref "U2") (pin "D11") (pinfunction "VSS_D11_D11") (pintype "power_in"))
      (node (ref "U2") (pin "D2") (pinfunction "VSS_D2_D2") (pintype "power_in"))
      (node (ref "U2") (pin "D4") (pinfunction "VSS_D4_D4") (pintype "power_in"))
      (node (ref "U2") (pin "D9") (pinfunction "VSS_D9_D9") (pintype "power_in"))
      (node (ref "U2") (pin "E1") (pinfunction "VSS_E1_E1") (pintype "power_in"))
      (node (ref "U2") (pin "E12") (pinfunction "VSS_E12_E12") (pintype "power_in"))
      (node (ref "U2") (pin "E5") (pinfunction "VSS_E5_E5") (pintype "power_in"))
      (node (ref "U2") (pin "E8") (pinfunction "VSS_E8_E8") (pintype "power_in"))
      (node (ref "U2") (pin "G1") (pinfunction "VSS_G1_G1") (pintype "power_in"))
      (node (ref "U2") (pin "G10") (pinfunction "VSS_G10_G10") (pintype "power_in"))
      (node (ref "U2") (pin "G12") (pinfunction "VSS_G12_G12") (pintype "power_in"))
      (node (ref "U2") (pin "G3") (pinfunction "VSS_G3_G3") (pintype "power_in"))
      (node (ref "U2") (pin "G5") (pinfunction "VSS_G5_G5") (pintype "power_in"))
      (node (ref "U2") (pin "G8") (pinfunction "VSS_G8_G8") (pintype "power_in"))
      (node (ref "U2") (pin "J1") (pinfunction "VSS_J1_J1") (pintype "power_in"))
      (node (ref "U2") (pin "J10") (pinfunction "VSS_J10_J10") (pintype "power_in"))
      (node (ref "U2") (pin "J12") (pinfunction "VSS_J12_J12") (pintype "power_in"))
      (node (ref "U2") (pin "J3") (pinfunction "VSS_J3_J3") (pintype "power_in"))
      (node (ref "U2") (pin "K11") (pinfunction "VSS_K11_K11") (pintype "power_in"))
      (node (ref "U2") (pin "K2") (pinfunction "VSS_K2_K2") (pintype "power_in"))
      (node (ref "U2") (pin "K4") (pinfunction "VSS_K4_K4") (pintype "power_in"))
      (node (ref "U2") (pin "K9") (pinfunction "VSS_K9_K9") (pintype "power_in"))
      (node (ref "U2") (pin "N11") (pinfunction "VSS_N11_N11") (pintype "power_in"))
      (node (ref "U2") (pin "N2") (pinfunction "VSS_N2_N2") (pintype "power_in"))
      (node (ref "U2") (pin "N4") (pinfunction "VSS_N4_N4") (pintype "power_in"))
      (node (ref "U2") (pin "N9") (pinfunction "VSS_N9_N9") (pintype "power_in"))
      (node (ref "U2") (pin "P1") (pinfunction "VSS_P1_P1") (pintype "power_in"))
      (node (ref "U2") (pin "P10") (pinfunction "VSS_P10_P10") (pintype "power_in"))
      (node (ref "U2") (pin "P12") (pinfunction "VSS_P12_P12") (pintype "power_in"))
      (node (ref "U2") (pin "P3") (pinfunction "VSS_P3_P3") (pintype "power_in"))
      (node (ref "U2") (pin "T1") (pinfunction "VSS_T1_T1") (pintype "power_in"))
      (node (ref "U2") (pin "T10") (pinfunction "VSS_T10_T10") (pintype "power_in"))
      (node (ref "U2") (pin "T12") (pinfunction "VSS_T12_T12") (pintype "power_in"))
      (node (ref "U2") (pin "T3") (pinfunction "VSS_T3_T3") (pintype "power_in"))
      (node (ref "U2") (pin "T5") (pinfunction "VSS_T5_T5") (pintype "power_in"))
      (node (ref "U2") (pin "T8") (pinfunction "VSS_T8_T8") (pintype "power_in"))
      (node (ref "U2") (pin "V1") (pinfunction "VSS_V1_V1") (pintype "power_in"))
      (node (ref "U2") (pin "V12") (pinfunction "VSS_V12_V12") (pintype "power_in"))
      (node (ref "U2") (pin "V5") (pinfunction "VSS_V5_V5") (pintype "power_in"))
      (node (ref "U2") (pin "V8") (pinfunction "VSS_V8_V8") (pintype "power_in"))
      (node (ref "U2") (pin "W11") (pinfunction "VSS_W11_W11") (pintype "power_in"))
      (node (ref "U2") (pin "W2") (pinfunction "VSS_W2_W2") (pintype "power_in"))
      (node (ref "U2") (pin "W4") (pinfunction "VSS_W4_W4") (pintype "power_in"))
      (node (ref "U2") (pin "W9") (pinfunction "VSS_W9_W9") (pintype "power_in"))
      (node (ref "U2") (pin "Y1") (pinfunction "VSS_Y1_Y1") (pintype "power_in"))
      (node (ref "U2") (pin "Y12") (pinfunction "VSS_Y12_Y12") (pintype "power_in"))
      (node (ref "U2") (pin "Y5") (pinfunction "VSS_Y5_Y5") (pintype "power_in"))
      (node (ref "U2") (pin "Y8") (pinfunction "VSS_Y8_Y8") (pintype "power_in"))
    )
    (net (code "74") (name "NVCC_DRAM_1V1") (class "Default")
      (node (ref "C101") (pin "1") (pinfunction "1_1") (pintype "passive"))
      (node (ref "C102") (pin "1") (pinfunction "1_1") (pintype "passive"))
      (node (ref "C103") (pin "1") (pinfunction "1_1") (pintype "passive"))
      (node (ref "C104") (pin "1") (pinfunction "1_1") (pintype "passive"))
      (node (ref "C105") (pin "1") (pinfunction "1_1") (pintype "passive"))
      (node (ref "C106") (pin "1") (pinfunction "1_1") (pintype "passive"))
      (node (ref "C107") (pin "1") (pinfunction "1_1") (pintype "passive"))
      (node (ref "C108") (pin "1") (pinfunction "1_1") (pintype "passive"))
      (node (ref "C109") (pin "1") (pinfunction "1_1") (pintype "passive"))
      (node (ref "C110") (pin "1") (pinfunction "1_1") (pintype "passive"))
      (node (ref "C111") (pin "1") (pinfunction "1_1") (pintype "passive"))
      (node (ref "C112") (pin "1") (pinfunction "1_1") (pintype "passive"))
      (node (ref "C113") (pin "1") (pinfunction "1_1") (pintype "passive"))
      (node (ref "C114") (pin "1") (pinfunction "1_1") (pintype "passive"))
      (node (ref "C115") (pin "1") (pinfunction "1_1") (pintype "passive"))
      (node (ref "C116") (pin "1") (pinfunction "1_1") (pintype "passive"))
      (node (ref "C117") (pin "1") (pinfunction "1_1") (pintype "passive"))
      (node (ref "C118") (pin "1") (pinfunction "1_1") (pintype "passive"))
      (node (ref "C144") (pin "1") (pinfunction "1_1") (pintype "passive"))
      (node (ref "C145") (pin "1") (pinfunction "1_1") (pintype "passive"))
      (node (ref "C146") (pin "1") (pinfunction "1_1") (pintype "passive"))
      (node (ref "C147") (pin "1") (pinfunction "1_1") (pintype "passive"))
      (node (ref "C148") (pin "1") (pinfunction "1_1") (pintype "passive"))
      (node (ref "C149") (pin "1") (pinfunction "1_1") (pintype "passive"))
      (node (ref "C150") (pin "1") (pinfunction "1_1") (pintype "passive"))
      (node (ref "C151") (pin "1") (pinfunction "1_1") (pintype "passive"))
      (node (ref "C152") (pin "1") (pinfunction "1_1") (pintype "passive"))
      (node (ref "C153") (pin "1") (pinfunction "1_1") (pintype "passive"))
      (node (ref "C154") (pin "1") (pinfunction "1_1") (pintype "passive"))
      (node (ref "C155") (pin "1") (pinfunction "1_1") (pintype "passive"))
      (node (ref "C156") (pin "1") (pinfunction "1_1") (pintype "passive"))
      (node (ref "C157") (pin "1") (pinfunction "1_1") (pintype "passive"))
      (node (ref "C158") (pin "1") (pinfunction "1_1") (pintype "passive"))
      (node (ref "C159") (pin "1") (pinfunction "1_1") (pintype "passive"))
      (node (ref "C160") (pin "1") (pinfunction "1_1") (pintype "passive"))
      (node (ref "R19") (pin "1") (pinfunction "1_1") (pintype "passive"))
      (node (ref "R20") (pin "1") (pinfunction "1_1") (pintype "passive"))
      (node (ref "U2") (pin "A4") (pinfunction "VDD2_A4_A4") (pintype "power_in"))
      (node (ref "U2") (pin "A9") (pinfunction "VDD2_A9_A9") (pintype "power_in"))
      (node (ref "U2") (pin "AA10") (pinfunction "VDDQ_AA10_AA10") (pintype "power_in"))
      (node (ref "U2") (pin "AA3") (pinfunction "VDDQ_AA3_AA3") (pintype "power_in"))
      (node (ref "U2") (pin "AA5") (pinfunction "VDDQ_AA5_AA5") (pintype "power_in"))
      (node (ref "U2") (pin "AA8") (pinfunction "VDDQ_AA8_AA8") (pintype "power_in"))
      (node (ref "U2") (pin "AB4") (pinfunction "VDD2_AB4_AB4") (pintype "power_in"))
      (node (ref "U2") (pin "AB9") (pinfunction "VDD2_AB9_AB9") (pintype "power_in"))
      (node (ref "U2") (pin "B10") (pinfunction "VDDQ_B10_B10") (pintype "power_in"))
      (node (ref "U2") (pin "B3") (pinfunction "VDDQ_B3_B3") (pintype "power_in"))
      (node (ref "U2") (pin "B5") (pinfunction "VDDQ_B5_B5") (pintype "power_in"))
      (node (ref "U2") (pin "B8") (pinfunction "VDDQ_B8_B8") (pintype "power_in"))
      (node (ref "U2") (pin "D1") (pinfunction "VDDQ_D1_D1") (pintype "power_in"))
      (node (ref "U2") (pin "D12") (pinfunction "VDDQ_D12_D12") (pintype "power_in"))
      (node (ref "U2") (pin "D5") (pinfunction "VDDQ_D5_D5") (pintype "power_in"))
      (node (ref "U2") (pin "D8") (pinfunction "VDDQ_D8_D8") (pintype "power_in"))
      (node (ref "U2") (pin "F10") (pinfunction "VDDQ_F10_F10") (pintype "power_in"))
      (node (ref "U2") (pin "F3") (pinfunction "VDDQ_F3_F3") (pintype "power_in"))
      (node (ref "U2") (pin "F5") (pinfunction "VDD2_F5_F5") (pintype "power_in"))
      (node (ref "U2") (pin "F8") (pinfunction "VDD2_F8_F8") (pintype "power_in"))
      (node (ref "U2") (pin "G2") (pinfunction "ODT_CA_A_G2") (pintype "input"))
      (node (ref "U2") (pin "H1") (pinfunction "VDD2_H1_H1") (pintype "power_in"))
      (node (ref "U2") (pin "H12") (pinfunction "VDD2_H12_H12") (pintype "power_in"))
      (node (ref "U2") (pin "H5") (pinfunction "VDD2_H5_H5") (pintype "power_in"))
      (node (ref "U2") (pin "H8") (pinfunction "VDD2_H8_H8") (pintype "power_in"))
      (node (ref "U2") (pin "K1") (pinfunction "VDD2_K1_K1") (pintype "power_in"))
      (node (ref "U2") (pin "K10") (pinfunction "VDD2_K10_K10") (pintype "power_in"))
      (node (ref "U2") (pin "K12") (pinfunction "VDD2_K12_K12") (pintype "power_in"))
      (node (ref "U2") (pin "K3") (pinfunction "VDD2_K3_K3") (pintype "power_in"))
      (node (ref "U2") (pin "N1") (pinfunction "VDD2_N1_N1") (pintype "power_in"))
      (node (ref "U2") (pin "N10") (pinfunction "VDD2_N10_N10") (pintype "power_in"))
      (node (ref "U2") (pin "N12") (pinfunction "VDD2_N12_N12") (pintype "power_in"))
      (node (ref "U2") (pin "N3") (pinfunction "VDD2_N3_N3") (pintype "power_in"))
      (node (ref "U2") (pin "R1") (pinfunction "VDD2_R1_R1") (pintype "power_in"))
      (node (ref "U2") (pin "R12") (pinfunction "VDD2_R12_R12") (pintype "power_in"))
      (node (ref "U2") (pin "R5") (pinfunction "VDD2_R5_R5") (pintype "power_in"))
      (node (ref "U2") (pin "R8") (pinfunction "VDD2_R8_R8") (pintype "power_in"))
      (node (ref "U2") (pin "T2") (pinfunction "ODT_CA_B_T2") (pintype "input"))
      (node (ref "U2") (pin "U10") (pinfunction "VDDQ_U10_U10") (pintype "power_in"))
      (node (ref "U2") (pin "U3") (pinfunction "VDDQ_U3_U3") (pintype "power_in"))
      (node (ref "U2") (pin "U5") (pinfunction "VDD2_U5_U5") (pintype "power_in"))
      (node (ref "U2") (pin "U8") (pinfunction "VDD2_U8_U8") (pintype "power_in"))
      (node (ref "U2") (pin "W1") (pinfunction "VDDQ_W1_W1") (pintype "power_in"))
      (node (ref "U2") (pin "W12") (pinfunction "VDDQ_W12_W12") (pintype "power_in"))
      (node (ref "U2") (pin "W5") (pinfunction "VDDQ_W5_W5") (pintype "power_in"))
      (node (ref "U2") (pin "W8") (pinfunction "VDDQ_W8_W8") (pintype "power_in"))
    )
    (net (code "75") (name "Net-(U1A-DRAM_ZN)") (class "Default")
      (node (ref "R18") (pin "2") (pinfunction "2_2") (pintype "passive"))
      (node (ref "U1") (pin "P2") (pinfunction "DRAM_ZN_P2") (pintype "passive"))
    )
    (net (code "76") (name "VDD_1V8") (class "Default")
      (node (ref "C100") (pin "1") (pinfunction "1_1") (pintype "passive"))
      (node (ref "C93") (pin "1") (pinfunction "1_1") (pintype "passive"))
      (node (ref "C94") (pin "1") (pinfunction "1_1") (pintype "passive"))
      (node (ref "C95") (pin "1") (pinfunction "1_1") (pintype "passive"))
      (node (ref "C96") (pin "1") (pinfunction "1_1") (pintype "passive"))
      (node (ref "C97") (pin "1") (pinfunction "1_1") (pintype "passive"))
      (node (ref "C98") (pin "1") (pinfunction "1_1") (pintype "passive"))
      (node (ref "C99") (pin "1") (pinfunction "1_1") (pintype "passive"))
      (node (ref "U2") (pin "F1") (pinfunction "VDD1_F1_F1") (pintype "power_in"))
      (node (ref "U2") (pin "F12") (pinfunction "VDD1_F12_F12") (pintype "power_in"))
      (node (ref "U2") (pin "G4") (pinfunction "VDD1_G4_G4") (pintype "power_in"))
      (node (ref "U2") (pin "G9") (pinfunction "VDD1_G9_G9") (pintype "power_in"))
      (node (ref "U2") (pin "T4") (pinfunction "VDD1_T4_T4") (pintype "power_in"))
      (node (ref "U2") (pin "T9") (pinfunction "VDD1_T9_T9") (pintype "power_in"))
      (node (ref "U2") (pin "U1") (pinfunction "VDD1_U1_U1") (pintype "power_in"))
      (node (ref "U2") (pin "U12") (pinfunction "VDD1_U12_U12") (pintype "power_in"))
    )
    (net (code "77") (name "unconnected-(U1A-DRAM_AC06{slash}--_{slash}_ACT_n_{slash}_A15-PadF6)") (class "Default")
      (node (ref "U1") (pin "F6") (pinfunction "DRAM_AC06/--_/_ACT_n_/_A15_F6") (pintype "passive"))
    )
    (net (code "78") (name "unconnected-(U1A-DRAM_AC07{slash}--_{slash}_A9_{slash}_A9-PadJ5)") (class "Default")
      (node (ref "U1") (pin "J5") (pinfunction "DRAM_AC07/--_/_A9_/_A9_J5") (pintype "passive"))
    )
    (net (code "79") (name "unconnected-(U1A-DRAM_AC14{slash}_--_{slash}_A4_{slash}_A4-PadK5)") (class "Default")
      (node (ref "U1") (pin "K5") (pinfunction "DRAM_AC14/_--_/_A4_/_A4_K5") (pintype "passive+no_connect"))
    )
    (net (code "80") (name "unconnected-(U1A-DRAM_AC15{slash}--_{slash}_A3_{slash}_A3-PadN6)") (class "Default")
      (node (ref "U1") (pin "N6") (pinfunction "DRAM_AC15/--_/_A3_/_A3_N6") (pintype "passive"))
    )
    (net (code "81") (name "unconnected-(U1A-DRAM_AC16{slash}--_{slash}_CK_t_A_{slash}_CK_A-PadM1)") (class "Default")
      (node (ref "U1") (pin "M1") (pinfunction "DRAM_AC16/--_/_CK_t_A_/_CK_A_M1") (pintype "passive"))
    )
    (net (code "82") (name "unconnected-(U1A-DRAM_AC17{slash}--_{slash}_CK_c_A_{slash}_CK#_A-PadM2)") (class "Default")
      (node (ref "U1") (pin "M2") (pinfunction "DRAM_AC17/--_/_CK_c_A_/_CK#_A_M2") (pintype "passive"))
    )
    (net (code "83") (name "unconnected-(U1A-DRAM_AC19{slash}MTEST_{slash}_MTEST_{slash}_MTEST-PadN2)") (class "Default")
      (node (ref "U1") (pin "N2") (pinfunction "DRAM_AC19/MTEST_/_MTEST_/_MTEST_N2") (pintype "passive"))
    )
    (net (code "84") (name "unconnected-(U1A-DRAM_AC26{slash}--_{slash}_BA1_{slash}_BA1-PadN1)") (class "Default")
      (node (ref "U1") (pin "N1") (pinfunction "DRAM_AC26/--_/_BA1_/_BA1_N1") (pintype "passive"))
    )
    (net (code "85") (name "unconnected-(U1A-DRAM_AC27{slash}--_{slash}_PARITY_{slash}_---PadR6)") (class "Default")
      (node (ref "U1") (pin "R6") (pinfunction "DRAM_AC27/--_/_PARITY_/_--_R6") (pintype "passive"))
    )
    (net (code "86") (name "unconnected-(U1A-DRAM_AC34{slash}_--_{slash}WE_n(A14){slash}WE#-PadT1)") (class "Default")
      (node (ref "U1") (pin "T1") (pinfunction "DRAM_AC34/_--_/WE_n(A14)/WE#_T1") (pintype "passive+no_connect"))
    )
    (net (code "87") (name "unconnected-(U1A-DRAM_AC35{slash}--_{slash}_RAS_n(A16)_{slash}_RAS#-PadT2)") (class "Default")
      (node (ref "U1") (pin "T2") (pinfunction "DRAM_AC35/--_/_RAS_n(A16)_/_RAS#_T2") (pintype "passive"))
    )
    (net (code "88") (name "unconnected-(U1A-DRAM_AC36{slash}--_{slash}_ODT0_{slash}_ODT0-PadV5)") (class "Default")
      (node (ref "U1") (pin "V5") (pinfunction "DRAM_AC36/--_/_ODT0_/_ODT0_V5") (pintype "passive"))
    )
    (net (code "89") (name "unconnected-(U1A-DRAM_AC37{slash}--_{slash}_ODT1_{slash}_ODT1-PadW5)") (class "Default")
      (node (ref "U1") (pin "W5") (pinfunction "DRAM_AC37/--_/_ODT1_/_ODT1_W5") (pintype "passive"))
    )
    (net (code "90") (name "unconnected-(U1A-DRAM_AC38{slash}--_{slash}_CS1_n_{slash}_CS1#-PadAB6)") (class "Default")
      (node (ref "U1") (pin "AB6") (pinfunction "DRAM_AC38/--_/_CS1_n_/_CS1#_AB6") (pintype "passive"))
    )
    (net (code "91") (name "unconnected-(U1A-DRAM_ALERT_N-PadR2)") (class "Default")
      (node (ref "U1") (pin "R2") (pinfunction "DRAM_ALERT_N_R2") (pintype "passive+no_connect"))
    )
    (net (code "92") (name "unconnected-(U2A-DNU_A1-PadA1)") (class "Default")
      (node (ref "U2") (pin "A1") (pinfunction "DNU_A1_A1") (pintype "passive+no_connect"))
    )
    (net (code "93") (name "unconnected-(U2A-DNU_A2-PadA2)") (class "Default")
      (node (ref "U2") (pin "A2") (pinfunction "DNU_A2_A2") (pintype "passive+no_connect"))
    )
    (net (code "94") (name "unconnected-(U2A-DNU_A11-PadA11)") (class "Default")
      (node (ref "U2") (pin "A11") (pinfunction "DNU_A11_A11") (pintype "passive+no_connect"))
    )
    (net (code "95") (name "unconnected-(U2A-DNU_A12-PadA12)") (class "Default")
      (node (ref "U2") (pin "A12") (pinfunction "DNU_A12_A12") (pintype "passive+no_connect"))
    )
    (net (code "96") (name "unconnected-(U2A-DNU_AA1-PadAA1)") (class "Default")
      (node (ref "U2") (pin "AA1") (pinfunction "DNU_AA1_AA1") (pintype "passive+no_connect"))
    )
    (net (code "97") (name "unconnected-(U2A-DNU_AA12-PadAA12)") (class "Default")
      (node (ref "U2") (pin "AA12") (pinfunction "DNU_AA12_AA12") (pintype "passive+no_connect"))
    )
    (net (code "98") (name "unconnected-(U2A-DNU_AB1-PadAB1)") (class "Default")
      (node (ref "U2") (pin "AB1") (pinfunction "DNU_AB1_AB1") (pintype "passive+no_connect"))
    )
    (net (code "99") (name "unconnected-(U2A-DNU_AB2-PadAB2)") (class "Default")
      (node (ref "U2") (pin "AB2") (pinfunction "DNU_AB2_AB2") (pintype "passive+no_connect"))
    )
    (net (code "100") (name "unconnected-(U2A-DNU_AB11-PadAB11)") (class "Default")
      (node (ref "U2") (pin "AB11") (pinfunction "DNU_AB11_AB11") (pintype "passive+no_connect"))
    )
    (net (code "101") (name "unconnected-(U2A-DNU_AB12-PadAB12)") (class "Default")
      (node (ref "U2") (pin "AB12") (pinfunction "DNU_AB12_AB12") (pintype "passive+no_connect"))
    )
    (net (code "102") (name "unconnected-(U2A-DNU_B1-PadB1)") (class "Default")
      (node (ref "U2") (pin "B1") (pinfunction "DNU_B1_B1") (pintype "passive+no_connect"))
    )
    (net (code "103") (name "unconnected-(U2A-DNU_B12-PadB12)") (class "Default")
      (node (ref "U2") (pin "B12") (pinfunction "DNU_B12_B12") (pintype "passive+no_connect"))
    )
    (net (code "104") (name "unconnected-(U2A-NC_G11-PadG11)") (class "Default")
      (node (ref "U2") (pin "G11") (pinfunction "NC_G11_G11") (pintype "passive"))
    )
    (net (code "105") (name "unconnected-(U2A-NC_K5-PadK5)") (class "Default")
      (node (ref "U2") (pin "K5") (pinfunction "NC_K5_K5") (pintype "passive"))
    )
    (net (code "106") (name "unconnected-(U2A-NC_K8-PadK8)") (class "Default")
      (node (ref "U2") (pin "K8") (pinfunction "NC_K8_K8") (pintype "passive"))
    )
    (net (code "107") (name "unconnected-(U2A-NC_N5-PadN5)") (class "Default")
      (node (ref "U2") (pin "N5") (pinfunction "NC_N5_N5") (pintype "passive"))
    )
    (net (code "108") (name "unconnected-(U2A-NC_N8-PadN8)") (class "Default")
      (node (ref "U2") (pin "N8") (pinfunction "NC_N8_N8") (pintype "passive"))
    )
  )
)
